# Task12PDS_PCBver9.net
KiCad netlist of a schematic drawn in EAGLE
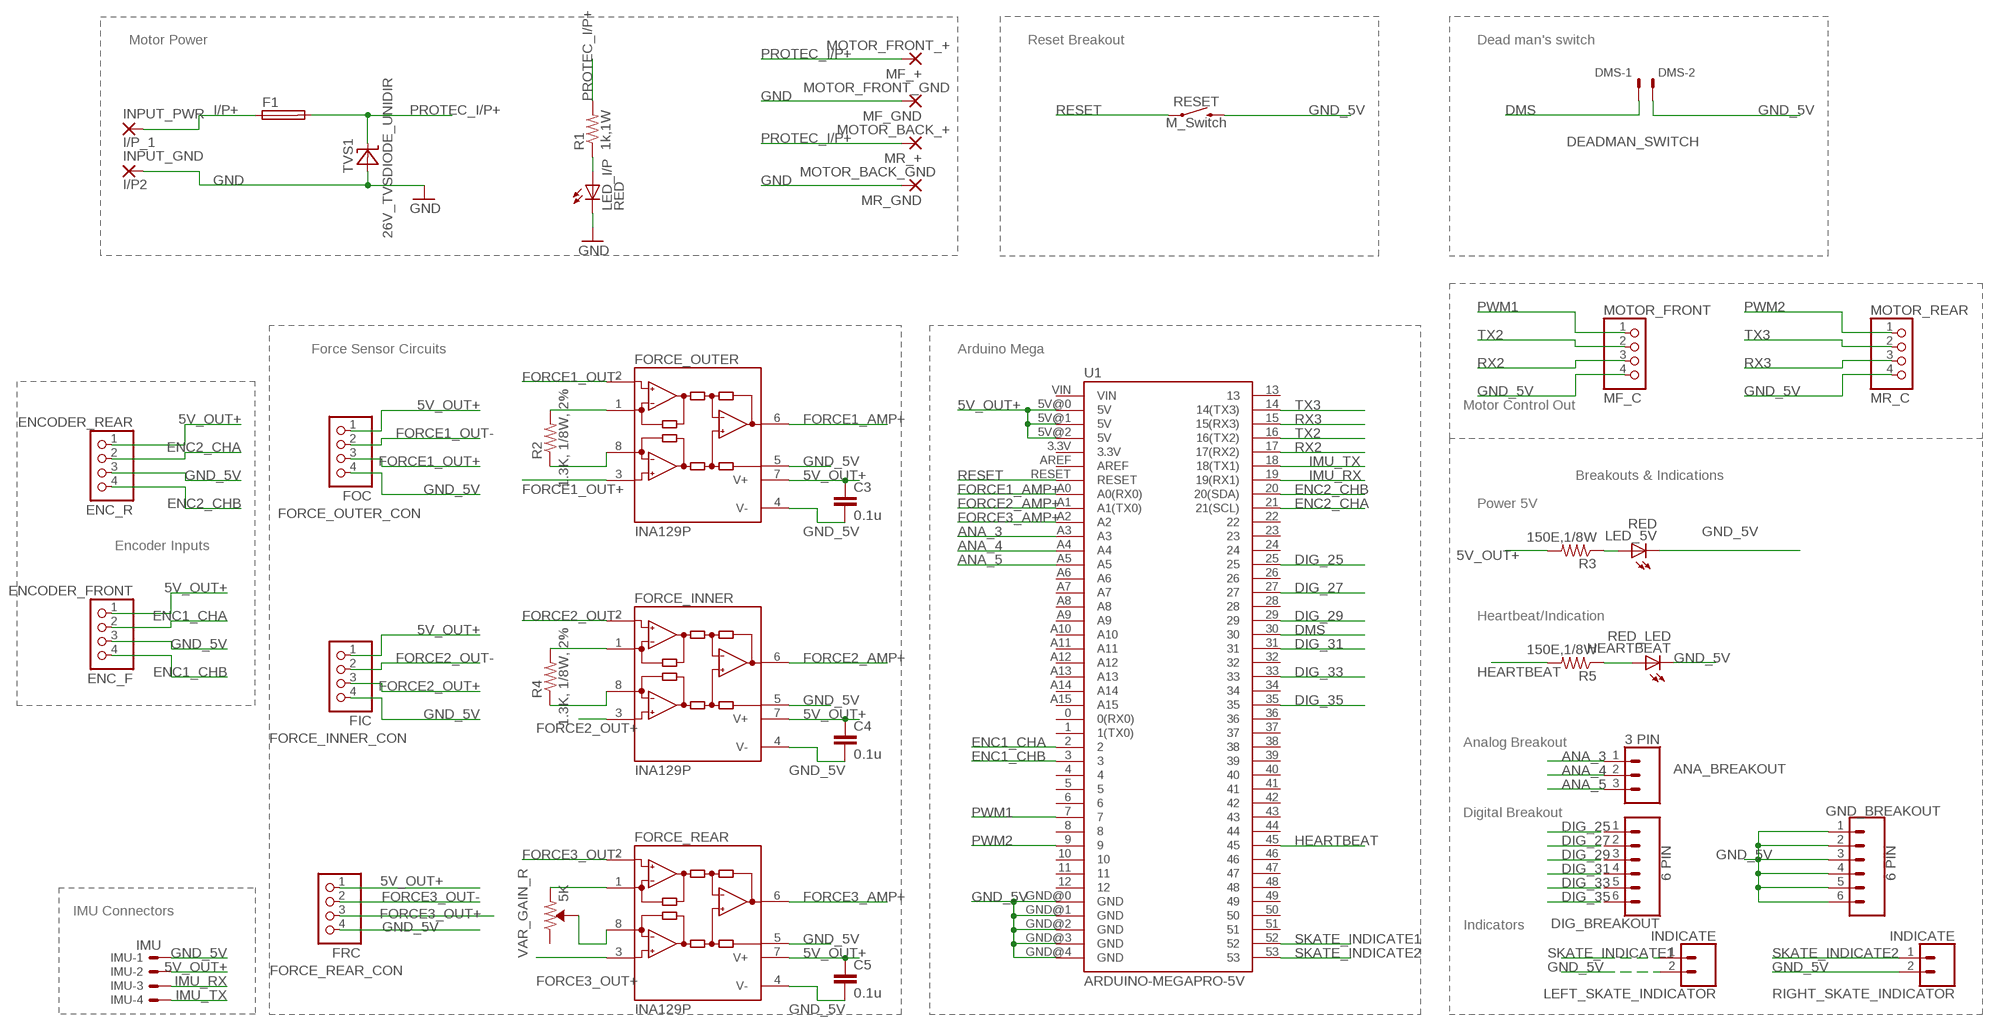
[diagram p0: schematic, sheet 1]

(export (version "E")
  (design (tool "Eeschema 10.0.6"))
  (components
    (comp (ref "ANA_BREAKOUT")
      (value "3 PIN")
      (footprint "eagle-import:1X03")
      (libsource (lib "eagle-import") (part "CONN_03"))
    )
    (comp (ref "C3")
      (value "0.1u")
      (footprint "eagle-import:C1206")
      (libsource (lib "eagle-import") (part "C-EUC1206"))
    )
    (comp (ref "C4")
      (value "0.1u")
      (footprint "eagle-import:C1206")
      (libsource (lib "eagle-import") (part "C-EUC1206"))
    )
    (comp (ref "C5")
      (value "0.1u")
      (footprint "eagle-import:C1206")
      (libsource (lib "eagle-import") (part "C-EUC1206"))
    )
    (comp (ref "DIG_BREAKOUT")
      (value "6 PIN")
      (footprint "eagle-import:1X06")
      (libsource (lib "eagle-import") (part "CONN_06SILK_FEMALE_PTH"))
    )
    (comp (ref "DMS")
      (value "DEADMAN_SWITCH")
      (footprint "eagle-import:22-23-2021")
      (fields (field (name "MF") "MOLEX") (field (name "MPN") "22-23-2021"))
      (libsource (lib "eagle-import") (part "22-23-2021"))
    )
    (comp (ref "ENCODER_FRONT")
      (value "ENC_F")
      (footprint "eagle-import:1X04_90")
      (libsource (lib "eagle-import") (part "PINHD-1X4/90"))
    )
    (comp (ref "ENCODER_REAR")
      (value "ENC_R")
      (footprint "eagle-import:1X04_90")
      (libsource (lib "eagle-import") (part "PINHD-1X4/90"))
    )
    (comp (ref "F1")
      (value "FASTBLOW_FUSE_10A")
      (footprint "eagle-import:TE5")
      (libsource (lib "eagle-import") (part "TE5"))
    )
    (comp (ref "FORCE_INNER")
      (value "INA129P")
      (footprint "eagle-import:DIL08")
      (fields (field (name "MF") "TEXAS INSTRUMENTS"))
      (libsource (lib "eagle-import") (part "INA129P"))
    )
    (comp (ref "FORCE_INNER_CON")
      (value "FIC")
      (footprint "eagle-import:1X04_90")
      (libsource (lib "eagle-import") (part "PINHD-1X4/90"))
    )
    (comp (ref "FORCE_OUTER")
      (value "INA129P")
      (footprint "eagle-import:DIL08")
      (fields (field (name "MF") "TEXAS INSTRUMENTS"))
      (libsource (lib "eagle-import") (part "INA129P"))
    )
    (comp (ref "FORCE_OUTER_CON")
      (value "FOC")
      (footprint "eagle-import:1X04_90")
      (libsource (lib "eagle-import") (part "PINHD-1X4/90"))
    )
    (comp (ref "FORCE_REAR")
      (value "INA129P")
      (footprint "eagle-import:DIL08")
      (fields (field (name "MF") "TEXAS INSTRUMENTS"))
      (libsource (lib "eagle-import") (part "INA129P"))
    )
    (comp (ref "FORCE_REAR_CON")
      (value "FRC")
      (footprint "eagle-import:1X04_90")
      (libsource (lib "eagle-import") (part "PINHD-1X4/90"))
    )
    (comp (ref "GND_BREAKOUT")
      (value "6 PIN")
      (footprint "eagle-import:1X06")
      (libsource (lib "eagle-import") (part "CONN_06SILK_FEMALE_PTH"))
    )
    (comp (ref "HEARTBEAT")
      (value "RED_LED")
      (footprint "eagle-import:1206")
      (libsource (lib "eagle-import") (part "LEDSMT1206"))
    )
    (comp (ref "IMU")
      (value "IMU")
      (footprint "eagle-import:22-23-2041")
      (fields (field (name "MF") "MOLEX") (field (name "MPN") "22-23-2041"))
      (libsource (lib "eagle-import") (part "22-23-2041"))
    )
    (comp (ref "INPUT_GND")
      (value "I/P2")
      (footprint "eagle-import:3,81_1,1")
      (libsource (lib "eagle-import") (part "WIREPAD3,81/1,1"))
    )
    (comp (ref "INPUT_PWR")
      (value "I/P_1")
      (footprint "eagle-import:3,81_1,1")
      (libsource (lib "eagle-import") (part "WIREPAD3,81/1,1"))
    )
    (comp (ref "LED_5V")
      (value "RED")
      (footprint "eagle-import:1206")
      (libsource (lib "eagle-import") (part "LEDSMT1206"))
    )
    (comp (ref "LED_I/P")
      (value "RED")
      (footprint "eagle-import:1206")
      (libsource (lib "eagle-import") (part "LEDSMT1206"))
    )
    (comp (ref "LEFT_SKATE_INDICATOR")
      (value "INDICATE")
      (footprint "eagle-import:1X02")
      (libsource (lib "eagle-import") (part "CONN_02"))
    )
    (comp (ref "MF_+")
      (value "MOTOR_FRONT_+")
      (footprint "eagle-import:3,81_1,1")
      (libsource (lib "eagle-import") (part "WIREPAD3,81/1,1"))
    )
    (comp (ref "MF_GND")
      (value "MOTOR_FRONT_GND")
      (footprint "eagle-import:3,81_1,1")
      (libsource (lib "eagle-import") (part "WIREPAD3,81/1,1"))
    )
    (comp (ref "MOTOR_FRONT")
      (value "MF_C")
      (footprint "eagle-import:1X04_90")
      (libsource (lib "eagle-import") (part "PINHD-1X4/90"))
    )
    (comp (ref "MOTOR_REAR")
      (value "MR_C")
      (footprint "eagle-import:1X04_90")
      (libsource (lib "eagle-import") (part "PINHD-1X4/90"))
    )
    (comp (ref "MR_+")
      (value "MOTOR_BACK_+")
      (footprint "eagle-import:3,81_1,1")
      (libsource (lib "eagle-import") (part "WIREPAD3,81/1,1"))
    )
    (comp (ref "MR_GND")
      (value "MOTOR_BACK_GND")
      (footprint "eagle-import:3,81_1,1")
      (libsource (lib "eagle-import") (part "WIREPAD3,81/1,1"))
    )
    (comp (ref "R1")
      (value "1k,1W")
      (footprint "eagle-import:M1206")
      (libsource (lib "eagle-import") (part "R-US_M1206"))
    )
    (comp (ref "R2")
      (value "1.3K, 1/8W, 2%")
      (footprint "eagle-import:M1206")
      (libsource (lib "eagle-import") (part "R-US_M1206"))
    )
    (comp (ref "R3")
      (value "150E,1/8W")
      (footprint "eagle-import:M1206")
      (libsource (lib "eagle-import") (part "R-US_M1206"))
    )
    (comp (ref "R4")
      (value "1.3K, 1/8W, 2%")
      (footprint "eagle-import:M1206")
      (libsource (lib "eagle-import") (part "R-US_M1206"))
    )
    (comp (ref "R5")
      (value "150E,1/8W")
      (footprint "eagle-import:M1206")
      (libsource (lib "eagle-import") (part "R-US_M1206"))
    )
    (comp (ref "RESET")
      (value "M_Switch")
      (footprint "eagle-import:TACTILE_SWITCH_PTH_6.0MM")
      (libsource (lib "eagle-import") (part "MOMENTARY-SWITCH-SPST-PTH-6.0MM"))
    )
    (comp (ref "RIGHT_SKATE_INDICATOR")
      (value "INDICATE")
      (footprint "eagle-import:1X02")
      (libsource (lib "eagle-import") (part "CONN_02"))
    )
    (comp (ref "TVS1")
      (value "26V_TVSDIODE_UNIDIR")
      (footprint "eagle-import:DO214AC")
      (libsource (lib "eagle-import") (part "26V_TVSDIODE_UNIDIR"))
    )
    (comp (ref "U1")
      (value "ARDUINO-MEGAPRO-5V")
      (footprint "eagle-import:ARDUINO_MEGA-PRO-5V")
      (libsource (lib "eagle-import") (part "ARDUINO-MEGAPRO-5V"))
    )
    (comp (ref "VAR_GAIN_R")
      (value "5K")
      (footprint "eagle-import:TRIMPOT-PTH-3386U")
      (libsource (lib "eagle-import") (part "TRIMPOT-PTH-10MM-KNOB-1/2W-10%"))
    )
  )
  (nets
    (net (code "1") (name "/5V_OUT+") (class "Default")
      (node (ref "C3") (pin "1") (pinfunction "1_1") (pintype "passive"))
      (node (ref "C4") (pin "1") (pinfunction "1_1") (pintype "passive"))
      (node (ref "C5") (pin "1") (pinfunction "1_1") (pintype "passive"))
      (node (ref "ENCODER_FRONT") (pin "1") (pinfunction "1_1") (pintype "passive"))
      (node (ref "ENCODER_REAR") (pin "1") (pinfunction "1_1") (pintype "passive"))
      (node (ref "FORCE_INNER") (pin "7") (pinfunction "V+_7") (pintype "power_in"))
      (node (ref "FORCE_INNER_CON") (pin "1") (pinfunction "1_1") (pintype "passive"))
      (node (ref "FORCE_OUTER") (pin "7") (pinfunction "V+_7") (pintype "power_in"))
      (node (ref "FORCE_OUTER_CON") (pin "1") (pinfunction "1_1") (pintype "passive"))
      (node (ref "FORCE_REAR") (pin "7") (pinfunction "V+_7") (pintype "power_in"))
      (node (ref "FORCE_REAR_CON") (pin "1") (pinfunction "1_1") (pintype "passive"))
      (node (ref "IMU") (pin "2") (pinfunction "S_2") (pintype "passive"))
      (node (ref "R3") (pin "2") (pinfunction "2_2") (pintype "passive"))
      (node (ref "U1") (pin "5V@0") (pinfunction "5V_5V@0") (pintype "bidirectional"))
      (node (ref "U1") (pin "5V@1") (pinfunction "5V_5V@1") (pintype "bidirectional"))
      (node (ref "U1") (pin "5V@2") (pinfunction "5V_5V@2") (pintype "bidirectional"))
    )
    (net (code "2") (name "/ANA_3") (class "Default")
      (node (ref "ANA_BREAKOUT") (pin "1") (pinfunction "1_1") (pintype "passive"))
      (node (ref "U1") (pin "A3") (pinfunction "A3_A3") (pintype "bidirectional"))
    )
    (net (code "3") (name "/ANA_4") (class "Default")
      (node (ref "ANA_BREAKOUT") (pin "2") (pinfunction "2_2") (pintype "passive"))
      (node (ref "U1") (pin "A4") (pinfunction "A4_A4") (pintype "bidirectional"))
    )
    (net (code "4") (name "/ANA_5") (class "Default")
      (node (ref "ANA_BREAKOUT") (pin "3") (pinfunction "3_3") (pintype "passive"))
      (node (ref "U1") (pin "A5") (pinfunction "A5_A5") (pintype "bidirectional"))
    )
    (net (code "5") (name "/DIG_25") (class "Default")
      (node (ref "DIG_BREAKOUT") (pin "1") (pinfunction "1_1") (pintype "passive"))
      (node (ref "U1") (pin "25") (pinfunction "25_25") (pintype "bidirectional"))
    )
    (net (code "6") (name "/DIG_27") (class "Default")
      (node (ref "DIG_BREAKOUT") (pin "2") (pinfunction "2_2") (pintype "passive"))
      (node (ref "U1") (pin "27") (pinfunction "27_27") (pintype "bidirectional"))
    )
    (net (code "7") (name "/DIG_29") (class "Default")
      (node (ref "DIG_BREAKOUT") (pin "3") (pinfunction "3_3") (pintype "passive"))
      (node (ref "U1") (pin "29") (pinfunction "29_29") (pintype "bidirectional"))
    )
    (net (code "8") (name "/DIG_31") (class "Default")
      (node (ref "DIG_BREAKOUT") (pin "4") (pinfunction "4_4") (pintype "passive"))
      (node (ref "U1") (pin "31") (pinfunction "31_31") (pintype "bidirectional"))
    )
    (net (code "9") (name "/DIG_33") (class "Default")
      (node (ref "DIG_BREAKOUT") (pin "5") (pinfunction "5_5") (pintype "passive"))
      (node (ref "U1") (pin "33") (pinfunction "33_33") (pintype "bidirectional"))
    )
    (net (code "10") (name "/DIG_35") (class "Default")
      (node (ref "DIG_BREAKOUT") (pin "6") (pinfunction "6_6") (pintype "passive"))
      (node (ref "U1") (pin "35") (pinfunction "35_35") (pintype "bidirectional"))
    )
    (net (code "11") (name "/DMS") (class "Default")
      (node (ref "DMS") (pin "1") (pinfunction "S_1") (pintype "passive"))
      (node (ref "U1") (pin "30") (pinfunction "30_30") (pintype "bidirectional"))
    )
    (net (code "12") (name "/ENC1_CHA") (class "Default")
      (node (ref "ENCODER_FRONT") (pin "2") (pinfunction "2_2") (pintype "passive"))
      (node (ref "U1") (pin "2") (pinfunction "2_2") (pintype "bidirectional"))
    )
    (net (code "13") (name "/ENC1_CHB") (class "Default")
      (node (ref "ENCODER_FRONT") (pin "4") (pinfunction "4_4") (pintype "passive"))
      (node (ref "U1") (pin "3") (pinfunction "3_3") (pintype "bidirectional"))
    )
    (net (code "14") (name "/ENC2_CHA") (class "Default")
      (node (ref "ENCODER_REAR") (pin "2") (pinfunction "2_2") (pintype "passive"))
      (node (ref "U1") (pin "21") (pinfunction "21(SCL)_21") (pintype "bidirectional"))
    )
    (net (code "15") (name "/ENC2_CHB") (class "Default")
      (node (ref "ENCODER_REAR") (pin "4") (pinfunction "4_4") (pintype "passive"))
      (node (ref "U1") (pin "20") (pinfunction "20(SDA)_20") (pintype "bidirectional"))
    )
    (net (code "16") (name "/FORCE1_AMP+") (class "Default")
      (node (ref "FORCE_OUTER") (pin "6") (pinfunction "OUT_6") (pintype "output"))
      (node (ref "U1") (pin "A0") (pinfunction "A0(RX0)_A0") (pintype "bidirectional"))
    )
    (net (code "17") (name "/FORCE1_OUT+") (class "Default")
      (node (ref "FORCE_OUTER") (pin "3") (pinfunction "+IN_3") (pintype "input"))
      (node (ref "FORCE_OUTER_CON") (pin "3") (pinfunction "3_3") (pintype "passive"))
    )
    (net (code "18") (name "/FORCE1_OUT-") (class "Default")
      (node (ref "FORCE_OUTER") (pin "2") (pinfunction "-IN_2") (pintype "input"))
      (node (ref "FORCE_OUTER_CON") (pin "2") (pinfunction "2_2") (pintype "passive"))
    )
    (net (code "19") (name "/FORCE2_AMP+") (class "Default")
      (node (ref "FORCE_INNER") (pin "6") (pinfunction "OUT_6") (pintype "output"))
      (node (ref "U1") (pin "A1") (pinfunction "A1(TX0)_A1") (pintype "bidirectional"))
    )
    (net (code "20") (name "/FORCE2_OUT+") (class "Default")
      (node (ref "FORCE_INNER") (pin "3") (pinfunction "+IN_3") (pintype "input"))
      (node (ref "FORCE_INNER_CON") (pin "3") (pinfunction "3_3") (pintype "passive"))
    )
    (net (code "21") (name "/FORCE2_OUT-") (class "Default")
      (node (ref "FORCE_INNER") (pin "2") (pinfunction "-IN_2") (pintype "input"))
      (node (ref "FORCE_INNER_CON") (pin "2") (pinfunction "2_2") (pintype "passive"))
    )
    (net (code "22") (name "/FORCE3_AMP+") (class "Default")
      (node (ref "FORCE_REAR") (pin "6") (pinfunction "OUT_6") (pintype "output"))
      (node (ref "U1") (pin "A2") (pinfunction "A2_A2") (pintype "bidirectional"))
    )
    (net (code "23") (name "/FORCE3_OUT+") (class "Default")
      (node (ref "FORCE_REAR") (pin "3") (pinfunction "+IN_3") (pintype "input"))
      (node (ref "FORCE_REAR_CON") (pin "3") (pinfunction "3_3") (pintype "passive"))
    )
    (net (code "24") (name "/FORCE3_OUT-") (class "Default")
      (node (ref "FORCE_REAR") (pin "2") (pinfunction "-IN_2") (pintype "input"))
      (node (ref "FORCE_REAR_CON") (pin "2") (pinfunction "2_2") (pintype "passive"))
    )
    (net (code "25") (name "/GND_5V") (class "Default")
      (node (ref "C3") (pin "2") (pinfunction "2_2") (pintype "passive"))
      (node (ref "C4") (pin "2") (pinfunction "2_2") (pintype "passive"))
      (node (ref "C5") (pin "2") (pinfunction "2_2") (pintype "passive"))
      (node (ref "DMS") (pin "2") (pinfunction "S_2") (pintype "passive"))
      (node (ref "ENCODER_FRONT") (pin "3") (pinfunction "3_3") (pintype "passive"))
      (node (ref "ENCODER_REAR") (pin "3") (pinfunction "3_3") (pintype "passive"))
      (node (ref "FORCE_INNER") (pin "4") (pinfunction "V-_4") (pintype "power_in"))
      (node (ref "FORCE_INNER") (pin "5") (pinfunction "REF_5") (pintype "passive"))
      (node (ref "FORCE_INNER_CON") (pin "4") (pinfunction "4_4") (pintype "passive"))
      (node (ref "FORCE_OUTER") (pin "4") (pinfunction "V-_4") (pintype "power_in"))
      (node (ref "FORCE_OUTER") (pin "5") (pinfunction "REF_5") (pintype "passive"))
      (node (ref "FORCE_OUTER_CON") (pin "4") (pinfunction "4_4") (pintype "passive"))
      (node (ref "FORCE_REAR") (pin "4") (pinfunction "V-_4") (pintype "power_in"))
      (node (ref "FORCE_REAR") (pin "5") (pinfunction "REF_5") (pintype "passive"))
      (node (ref "FORCE_REAR_CON") (pin "4") (pinfunction "4_4") (pintype "passive"))
      (node (ref "GND_BREAKOUT") (pin "1") (pinfunction "1_1") (pintype "passive"))
      (node (ref "GND_BREAKOUT") (pin "2") (pinfunction "2_2") (pintype "passive"))
      (node (ref "GND_BREAKOUT") (pin "3") (pinfunction "3_3") (pintype "passive"))
      (node (ref "GND_BREAKOUT") (pin "4") (pinfunction "4_4") (pintype "passive"))
      (node (ref "GND_BREAKOUT") (pin "5") (pinfunction "5_5") (pintype "passive"))
      (node (ref "GND_BREAKOUT") (pin "6") (pinfunction "6_6") (pintype "passive"))
      (node (ref "HEARTBEAT") (pin "C") (pinfunction "C_C") (pintype "passive"))
      (node (ref "IMU") (pin "1") (pinfunction "S_1") (pintype "passive"))
      (node (ref "LED_5V") (pin "C") (pinfunction "C_C") (pintype "passive"))
      (node (ref "LEFT_SKATE_INDICATOR") (pin "2") (pinfunction "2_2") (pintype "passive"))
      (node (ref "MOTOR_FRONT") (pin "4") (pinfunction "4_4") (pintype "passive"))
      (node (ref "MOTOR_REAR") (pin "4") (pinfunction "4_4") (pintype "passive"))
      (node (ref "RESET") (pin "3") (pinfunction "2_3") (pintype "passive"))
      (node (ref "RIGHT_SKATE_INDICATOR") (pin "2") (pinfunction "2_2") (pintype "passive"))
      (node (ref "U1") (pin "GND@0") (pinfunction "GND_GND@0") (pintype "bidirectional"))
      (node (ref "U1") (pin "GND@1") (pinfunction "GND_GND@1") (pintype "bidirectional"))
      (node (ref "U1") (pin "GND@2") (pinfunction "GND_GND@2") (pintype "bidirectional"))
      (node (ref "U1") (pin "GND@3") (pinfunction "GND_GND@3") (pintype "bidirectional"))
      (node (ref "U1") (pin "GND@4") (pinfunction "GND_GND@4") (pintype "bidirectional"))
    )
    (net (code "26") (name "/HEARTBEAT") (class "Default")
      (node (ref "R5") (pin "2") (pinfunction "2_2") (pintype "passive"))
      (node (ref "U1") (pin "45") (pinfunction "45_45") (pintype "bidirectional"))
    )
    (net (code "27") (name "/IMU_RX") (class "Default")
      (node (ref "IMU") (pin "3") (pinfunction "S_3") (pintype "passive"))
      (node (ref "U1") (pin "19") (pinfunction "19(RX1)_19") (pintype "bidirectional"))
    )
    (net (code "28") (name "/IMU_TX") (class "Default")
      (node (ref "IMU") (pin "4") (pinfunction "S_4") (pintype "passive"))
      (node (ref "U1") (pin "18") (pinfunction "18(TX1)_18") (pintype "bidirectional"))
    )
    (net (code "29") (name "/I{slash}P+") (class "Default")
      (node (ref "F1") (pin "1") (pinfunction "1_1") (pintype "passive"))
      (node (ref "INPUT_PWR") (pin "1") (pinfunction "P_1") (pintype "passive"))
    )
    (net (code "30") (name "/PROTEC_I{slash}P+") (class "Default")
      (node (ref "F1") (pin "2") (pinfunction "2_2") (pintype "passive"))
      (node (ref "MF_+") (pin "1") (pinfunction "P_1") (pintype "passive"))
      (node (ref "MR_+") (pin "1") (pinfunction "P_1") (pintype "passive"))
      (node (ref "R1") (pin "2") (pinfunction "2_2") (pintype "passive"))
      (node (ref "TVS1") (pin "C") (pinfunction "C_C") (pintype "passive"))
    )
    (net (code "31") (name "/PWM1") (class "Default")
      (node (ref "MOTOR_FRONT") (pin "1") (pinfunction "1_1") (pintype "passive"))
      (node (ref "U1") (pin "7") (pinfunction "7_7") (pintype "bidirectional"))
    )
    (net (code "32") (name "/PWM2") (class "Default")
      (node (ref "MOTOR_REAR") (pin "1") (pinfunction "1_1") (pintype "passive"))
      (node (ref "U1") (pin "9") (pinfunction "9_9") (pintype "bidirectional"))
    )
    (net (code "33") (name "/RESET") (class "Default")
      (node (ref "RESET") (pin "1") (pinfunction "1_1") (pintype "passive"))
      (node (ref "U1") (pin "RESET") (pinfunction "RESET_RESET") (pintype "bidirectional"))
    )
    (net (code "34") (name "/RX2") (class "Default")
      (node (ref "MOTOR_FRONT") (pin "3") (pinfunction "3_3") (pintype "passive"))
      (node (ref "U1") (pin "17") (pinfunction "17(RX2)_17") (pintype "bidirectional"))
    )
    (net (code "35") (name "/RX3") (class "Default")
      (node (ref "MOTOR_REAR") (pin "3") (pinfunction "3_3") (pintype "passive"))
      (node (ref "U1") (pin "15") (pinfunction "15(RX3)_15") (pintype "bidirectional"))
    )
    (net (code "36") (name "/SKATE_INDICATE1") (class "Default")
      (node (ref "LEFT_SKATE_INDICATOR") (pin "1") (pinfunction "1_1") (pintype "passive"))
      (node (ref "U1") (pin "52") (pinfunction "52_52") (pintype "bidirectional"))
    )
    (net (code "37") (name "/SKATE_INDICATE2") (class "Default")
      (node (ref "RIGHT_SKATE_INDICATOR") (pin "1") (pinfunction "1_1") (pintype "passive"))
      (node (ref "U1") (pin "53") (pinfunction "53_53") (pintype "bidirectional"))
    )
    (net (code "38") (name "/TX2") (class "Default")
      (node (ref "MOTOR_FRONT") (pin "2") (pinfunction "2_2") (pintype "passive"))
      (node (ref "U1") (pin "16") (pinfunction "16(TX2)_16") (pintype "bidirectional"))
    )
    (net (code "39") (name "/TX3") (class "Default")
      (node (ref "MOTOR_REAR") (pin "2") (pinfunction "2_2") (pintype "passive"))
      (node (ref "U1") (pin "14") (pinfunction "14(TX3)_14") (pintype "bidirectional"))
    )
    (net (code "40") (name "GND") (class "Default")
      (node (ref "INPUT_GND") (pin "1") (pinfunction "P_1") (pintype "passive"))
      (node (ref "LED_I/P") (pin "C") (pinfunction "C_C") (pintype "passive"))
      (node (ref "MF_GND") (pin "1") (pinfunction "P_1") (pintype "passive"))
      (node (ref "MR_GND") (pin "1") (pinfunction "P_1") (pintype "passive"))
      (node (ref "TVS1") (pin "A") (pinfunction "A_A") (pintype "passive"))
    )
    (net (code "41") (name "Net-(FORCE_INNER-RG-Pad1)") (class "Default")
      (node (ref "FORCE_INNER") (pin "1") (pinfunction "RG_1") (pintype "passive"))
      (node (ref "R4") (pin "2") (pinfunction "2_2") (pintype "passive"))
    )
    (net (code "42") (name "Net-(FORCE_INNER-RG-Pad8)") (class "Default")
      (node (ref "FORCE_INNER") (pin "8") (pinfunction "RG_8") (pintype "passive"))
      (node (ref "R4") (pin "1") (pinfunction "1_1") (pintype "passive"))
    )
    (net (code "43") (name "Net-(FORCE_OUTER-RG-Pad1)") (class "Default")
      (node (ref "FORCE_OUTER") (pin "1") (pinfunction "RG_1") (pintype "passive"))
      (node (ref "R2") (pin "2") (pinfunction "2_2") (pintype "passive"))
    )
    (net (code "44") (name "Net-(FORCE_OUTER-RG-Pad8)") (class "Default")
      (node (ref "FORCE_OUTER") (pin "8") (pinfunction "RG_8") (pintype "passive"))
      (node (ref "R2") (pin "1") (pinfunction "1_1") (pintype "passive"))
    )
    (net (code "45") (name "Net-(HEARTBEAT-PadA)") (class "Default")
      (node (ref "HEARTBEAT") (pin "A") (pinfunction "A_A") (pintype "passive"))
      (node (ref "R5") (pin "1") (pinfunction "1_1") (pintype "passive"))
    )
    (net (code "46") (name "Net-(LED_5V-PadA)") (class "Default")
      (node (ref "LED_5V") (pin "A") (pinfunction "A_A") (pintype "passive"))
      (node (ref "R3") (pin "1") (pinfunction "1_1") (pintype "passive"))
    )
    (net (code "47") (name "Net-(LED_I/P-PadA)") (class "Default")
      (node (ref "LED_I/P") (pin "A") (pinfunction "A_A") (pintype "passive"))
      (node (ref "R1") (pin "1") (pinfunction "1_1") (pintype "passive"))
    )
    (net (code "48") (name "Net-(VAR_GAIN_R-CCW)") (class "Default")
      (node (ref "FORCE_REAR") (pin "1") (pinfunction "RG_1") (pintype "passive"))
      (node (ref "VAR_GAIN_R") (pin "1") (pinfunction "CCW_1") (pintype "passive"))
    )
    (net (code "49") (name "Net-(VAR_GAIN_R-WIPER)") (class "Default")
      (node (ref "FORCE_REAR") (pin "8") (pinfunction "RG_8") (pintype "passive"))
      (node (ref "VAR_GAIN_R") (pin "2") (pinfunction "WIPER_2") (pintype "passive"))
    )
    (net (code "50") (name "unconnected-(U1-0(RX0)-Pad0)") (class "Default")
      (node (ref "U1") (pin "0") (pinfunction "0(RX0)_0") (pintype "bidirectional"))
    )
    (net (code "51") (name "unconnected-(U1-1(TX0)-Pad1)") (class "Default")
      (node (ref "U1") (pin "1") (pinfunction "1(TX0)_1") (pintype "bidirectional"))
    )
    (net (code "52") (name "unconnected-(U1-Pad3.3V)") (class "Default")
      (node (ref "U1") (pin "3.3V") (pinfunction "3.3V_3.3V") (pintype "bidirectional"))
    )
    (net (code "53") (name "unconnected-(U1-Pad4)") (class "Default")
      (node (ref "U1") (pin "4") (pinfunction "4_4") (pintype "bidirectional"))
    )
    (net (code "54") (name "unconnected-(U1-Pad5)") (class "Default")
      (node (ref "U1") (pin "5") (pinfunction "5_5") (pintype "bidirectional"))
    )
    (net (code "55") (name "unconnected-(U1-Pad6)") (class "Default")
      (node (ref "U1") (pin "6") (pinfunction "6_6") (pintype "bidirectional"))
    )
    (net (code "56") (name "unconnected-(U1-Pad8)") (class "Default")
      (node (ref "U1") (pin "8") (pinfunction "8_8") (pintype "bidirectional"))
    )
    (net (code "57") (name "unconnected-(U1-Pad10)") (class "Default")
      (node (ref "U1") (pin "10") (pinfunction "10_10") (pintype "bidirectional"))
    )
    (net (code "58") (name "unconnected-(U1-Pad11)") (class "Default")
      (node (ref "U1") (pin "11") (pinfunction "11_11") (pintype "bidirectional"))
    )
    (net (code "59") (name "unconnected-(U1-Pad12)") (class "Default")
      (node (ref "U1") (pin "12") (pinfunction "12_12") (pintype "bidirectional"))
    )
    (net (code "60") (name "unconnected-(U1-Pad13)") (class "Default")
      (node (ref "U1") (pin "13") (pinfunction "13_13") (pintype "bidirectional"))
    )
    (net (code "61") (name "unconnected-(U1-Pad22)") (class "Default")
      (node (ref "U1") (pin "22") (pinfunction "22_22") (pintype "bidirectional"))
    )
    (net (code "62") (name "unconnected-(U1-Pad23)") (class "Default")
      (node (ref "U1") (pin "23") (pinfunction "23_23") (pintype "bidirectional"))
    )
    (net (code "63") (name "unconnected-(U1-Pad24)") (class "Default")
      (node (ref "U1") (pin "24") (pinfunction "24_24") (pintype "bidirectional"))
    )
    (net (code "64") (name "unconnected-(U1-Pad26)") (class "Default")
      (node (ref "U1") (pin "26") (pinfunction "26_26") (pintype "bidirectional"))
    )
    (net (code "65") (name "unconnected-(U1-Pad28)") (class "Default")
      (node (ref "U1") (pin "28") (pinfunction "28_28") (pintype "bidirectional"))
    )
    (net (code "66") (name "unconnected-(U1-Pad32)") (class "Default")
      (node (ref "U1") (pin "32") (pinfunction "32_32") (pintype "bidirectional"))
    )
    (net (code "67") (name "unconnected-(U1-Pad34)") (class "Default")
      (node (ref "U1") (pin "34") (pinfunction "34_34") (pintype "bidirectional"))
    )
    (net (code "68") (name "unconnected-(U1-Pad36)") (class "Default")
      (node (ref "U1") (pin "36") (pinfunction "36_36") (pintype "bidirectional"))
    )
    (net (code "69") (name "unconnected-(U1-Pad37)") (class "Default")
      (node (ref "U1") (pin "37") (pinfunction "37_37") (pintype "bidirectional"))
    )
    (net (code "70") (name "unconnected-(U1-Pad38)") (class "Default")
      (node (ref "U1") (pin "38") (pinfunction "38_38") (pintype "bidirectional"))
    )
    (net (code "71") (name "unconnected-(U1-Pad39)") (class "Default")
      (node (ref "U1") (pin "39") (pinfunction "39_39") (pintype "bidirectional"))
    )
    (net (code "72") (name "unconnected-(U1-Pad40)") (class "Default")
      (node (ref "U1") (pin "40") (pinfunction "40_40") (pintype "bidirectional"))
    )
    (net (code "73") (name "unconnected-(U1-Pad41)") (class "Default")
      (node (ref "U1") (pin "41") (pinfunction "41_41") (pintype "bidirectional"))
    )
    (net (code "74") (name "unconnected-(U1-Pad42)") (class "Default")
      (node (ref "U1") (pin "42") (pinfunction "42_42") (pintype "bidirectional"))
    )
    (net (code "75") (name "unconnected-(U1-Pad43)") (class "Default")
      (node (ref "U1") (pin "43") (pinfunction "43_43") (pintype "bidirectional"))
    )
    (net (code "76") (name "unconnected-(U1-Pad44)") (class "Default")
      (node (ref "U1") (pin "44") (pinfunction "44_44") (pintype "bidirectional"))
    )
    (net (code "77") (name "unconnected-(U1-Pad46)") (class "Default")
      (node (ref "U1") (pin "46") (pinfunction "46_46") (pintype "bidirectional"))
    )
    (net (code "78") (name "unconnected-(U1-Pad47)") (class "Default")
      (node (ref "U1") (pin "47") (pinfunction "47_47") (pintype "bidirectional"))
    )
    (net (code "79") (name "unconnected-(U1-Pad48)") (class "Default")
      (node (ref "U1") (pin "48") (pinfunction "48_48") (pintype "bidirectional"))
    )
    (net (code "80") (name "unconnected-(U1-Pad49)") (class "Default")
      (node (ref "U1") (pin "49") (pinfunction "49_49") (pintype "bidirectional"))
    )
    (net (code "81") (name "unconnected-(U1-Pad50)") (class "Default")
      (node (ref "U1") (pin "50") (pinfunction "50_50") (pintype "bidirectional"))
    )
    (net (code "82") (name "unconnected-(U1-Pad51)") (class "Default")
      (node (ref "U1") (pin "51") (pinfunction "51_51") (pintype "bidirectional"))
    )
    (net (code "83") (name "unconnected-(U1-PadA6)") (class "Default")
      (node (ref "U1") (pin "A6") (pinfunction "A6_A6") (pintype "bidirectional"))
    )
    (net (code "84") (name "unconnected-(U1-PadA7)") (class "Default")
      (node (ref "U1") (pin "A7") (pinfunction "A7_A7") (pintype "bidirectional"))
    )
    (net (code "85") (name "unconnected-(U1-PadA8)") (class "Default")
      (node (ref "U1") (pin "A8") (pinfunction "A8_A8") (pintype "bidirectional"))
    )
    (net (code "86") (name "unconnected-(U1-PadA9)") (class "Default")
      (node (ref "U1") (pin "A9") (pinfunction "A9_A9") (pintype "bidirectional"))
    )
    (net (code "87") (name "unconnected-(U1-PadA10)") (class "Default")
      (node (ref "U1") (pin "A10") (pinfunction "A10_A10") (pintype "bidirectional"))
    )
    (net (code "88") (name "unconnected-(U1-PadA11)") (class "Default")
      (node (ref "U1") (pin "A11") (pinfunction "A11_A11") (pintype "bidirectional"))
    )
    (net (code "89") (name "unconnected-(U1-PadA12)") (class "Default")
      (node (ref "U1") (pin "A12") (pinfunction "A12_A12") (pintype "bidirectional"))
    )
    (net (code "90") (name "unconnected-(U1-PadA13)") (class "Default")
      (node (ref "U1") (pin "A13") (pinfunction "A13_A13") (pintype "bidirectional"))
    )
    (net (code "91") (name "unconnected-(U1-PadA14)") (class "Default")
      (node (ref "U1") (pin "A14") (pinfunction "A14_A14") (pintype "bidirectional"))
    )
    (net (code "92") (name "unconnected-(U1-PadA15)") (class "Default")
      (node (ref "U1") (pin "A15") (pinfunction "A15_A15") (pintype "bidirectional"))
    )
    (net (code "93") (name "unconnected-(U1-PadAREF)") (class "Default")
      (node (ref "U1") (pin "AREF") (pinfunction "AREF_AREF") (pintype "bidirectional"))
    )
    (net (code "94") (name "unconnected-(U1-PadVIN)") (class "Default")
      (node (ref "U1") (pin "VIN") (pinfunction "VIN_VIN") (pintype "bidirectional"))
    )
    (net (code "95") (name "unconnected-(VAR_GAIN_R-CW-Pad3)") (class "Default")
      (node (ref "VAR_GAIN_R") (pin "3") (pinfunction "CW_3") (pintype "passive"))
    )
  )
)
